# Dcdc_12V0_3V3.net
KiCad netlist of a schematic drawn in Altium Designer
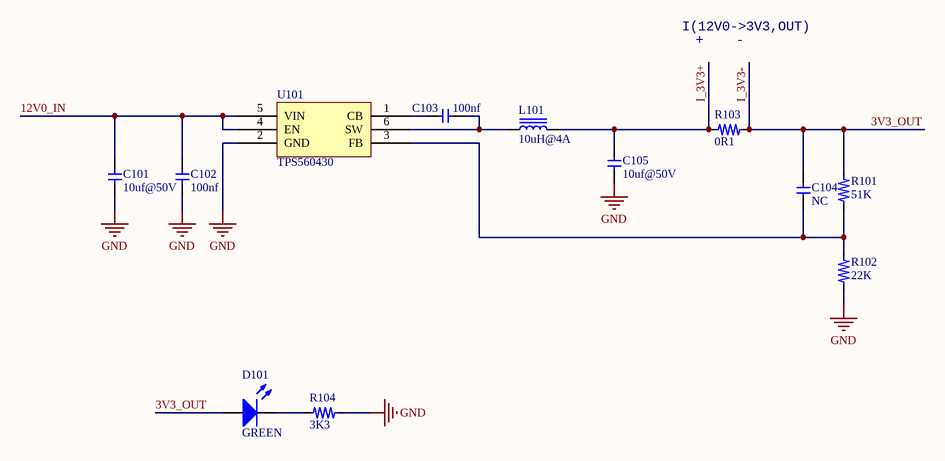
[diagram p0: Dcdc.12V0.+3V3.SchDoc]

(export (version "E")
  (design (tool "Eeschema 10.0.6"))
  (components
    (comp (ref "C101")
      (value "10uf@50V")
      (footprint "C1210")
      (fields (field (name "Comment") "Cap"))
      (libsource (lib "carrot_lib") (part "Cap"))
    )
    (comp (ref "C102")
      (value "100nf")
      (footprint "C0603")
      (fields (field (name "Comment") "Cap"))
      (libsource (lib "carrot_lib") (part "Cap"))
    )
    (comp (ref "C103")
      (value "100nf")
      (footprint "C0603")
      (fields (field (name "Comment") "Cap"))
      (libsource (lib "carrot_lib") (part "Cap"))
    )
    (comp (ref "C104")
      (value "NC")
      (footprint "C0603")
      (fields (field (name "Comment") "Cap"))
      (libsource (lib "carrot_lib") (part "Cap"))
    )
    (comp (ref "C105")
      (value "10uf@50V")
      (footprint "C1210")
      (fields (field (name "Comment") "Cap"))
      (libsource (lib "carrot_lib") (part "Cap"))
    )
    (comp (ref "D101")
      (value "GREEN")
      (footprint "LED0603")
      (fields (field (name "Comment") "LED"))
      (libsource (lib "carrot_lib") (part "LED"))
    )
    (comp (ref "L101")
      (value "10uH@4A")
      (footprint "L06063")
      (description "Magnetic-Core Inductor")
      (fields (field (name "Comment") "Inductor Iron"))
      (libsource (lib "carrot_lib") (part "Inductor Iron"))
    )
    (comp (ref "R101")
      (value "51K")
      (footprint "R0603")
      (description "电阻")
      (fields (field (name "Comment") "Res"))
      (libsource (lib "carrot_lib") (part "Res"))
    )
    (comp (ref "R102")
      (value "22K")
      (footprint "R0603")
      (description "电阻")
      (fields (field (name "Comment") "Res"))
      (libsource (lib "carrot_lib") (part "Res"))
    )
    (comp (ref "R103")
      (value "0R1")
      (footprint "R1206")
      (description "电阻")
      (fields (field (name "Comment") "Res"))
      (libsource (lib "carrot_lib") (part "Res"))
    )
    (comp (ref "R104")
      (value "3K3")
      (footprint "R0603")
      (description "电阻")
      (fields (field (name "Comment") "Res"))
      (libsource (lib "carrot_lib") (part "Res"))
    )
    (comp (ref "U101")
      (value "TPS560430")
      (footprint "TPS560430-SOT23-6")
      (description "TPS560430 SIMPLE SWITCHER® 4-V to 36-V, 600-mA Synchronous Step-Down Converter")
      (libsource (lib "carrot_lib") (part "TPS560430"))
    )
  )
  (nets
    (net (code "1") (name "/3V3_OUT") (class "Default")
      (node (ref "C104") (pin "1") (pinfunction "1_1") (pintype "passive"))
      (node (ref "D101") (pin "1") (pinfunction "A_1") (pintype "passive"))
      (node (ref "R101") (pin "2") (pinfunction "2_2") (pintype "passive"))
      (node (ref "R103") (pin "2") (pinfunction "2_2") (pintype "passive"))
    )
    (net (code "2") (name "/12V0_IN") (class "Default")
      (node (ref "C101") (pin "2") (pinfunction "2_2") (pintype "passive"))
      (node (ref "C102") (pin "2") (pinfunction "2_2") (pintype "passive"))
      (node (ref "U101") (pin "4") (pinfunction "EN_4") (pintype "passive"))
      (node (ref "U101") (pin "5") (pinfunction "VIN_5") (pintype "passive"))
    )
    (net (code "3") (name "/I_3V3+") (class "Default")
      (node (ref "C105") (pin "2") (pinfunction "2_2") (pintype "passive"))
      (node (ref "L101") (pin "2") (pinfunction "2_2") (pintype "passive"))
      (node (ref "R103") (pin "1") (pinfunction "1_1") (pintype "passive"))
    )
    (net (code "4") (name "GND") (class "Default")
      (node (ref "C101") (pin "1") (pinfunction "1_1") (pintype "passive"))
      (node (ref "C102") (pin "1") (pinfunction "1_1") (pintype "passive"))
      (node (ref "C105") (pin "1") (pinfunction "1_1") (pintype "passive"))
      (node (ref "R102") (pin "1") (pinfunction "1_1") (pintype "passive"))
      (node (ref "R104") (pin "1") (pinfunction "1_1") (pintype "passive"))
      (node (ref "U101") (pin "2") (pinfunction "GND_2") (pintype "passive"))
    )
    (net (code "5") (name "Net-(D101-K)") (class "Default")
      (node (ref "D101") (pin "2") (pinfunction "K_2") (pintype "passive"))
      (node (ref "R104") (pin "2") (pinfunction "2_2") (pintype "passive"))
    )
    (net (code "6") (name "Net-(U101-CB)") (class "Default")
      (node (ref "C103") (pin "2") (pinfunction "2_2") (pintype "passive"))
      (node (ref "U101") (pin "1") (pinfunction "CB_1") (pintype "passive"))
    )
    (net (code "7") (name "Net-(U101-FB)") (class "Default")
      (node (ref "C104") (pin "2") (pinfunction "2_2") (pintype "passive"))
      (node (ref "R101") (pin "1") (pinfunction "1_1") (pintype "passive"))
      (node (ref "R102") (pin "2") (pinfunction "2_2") (pintype "passive"))
      (node (ref "U101") (pin "3") (pinfunction "FB_3") (pintype "passive"))
    )
    (net (code "8") (name "Net-(U101-SW)") (class "Default")
      (node (ref "C103") (pin "1") (pinfunction "1_1") (pintype "passive"))
      (node (ref "L101") (pin "1") (pinfunction "1_1") (pintype "passive"))
      (node (ref "U101") (pin "6") (pinfunction "SW_6") (pintype "passive"))
    )
  )
)
